# main_board_CHM.net
KiCad netlist of a schematic drawn in Altium Designer
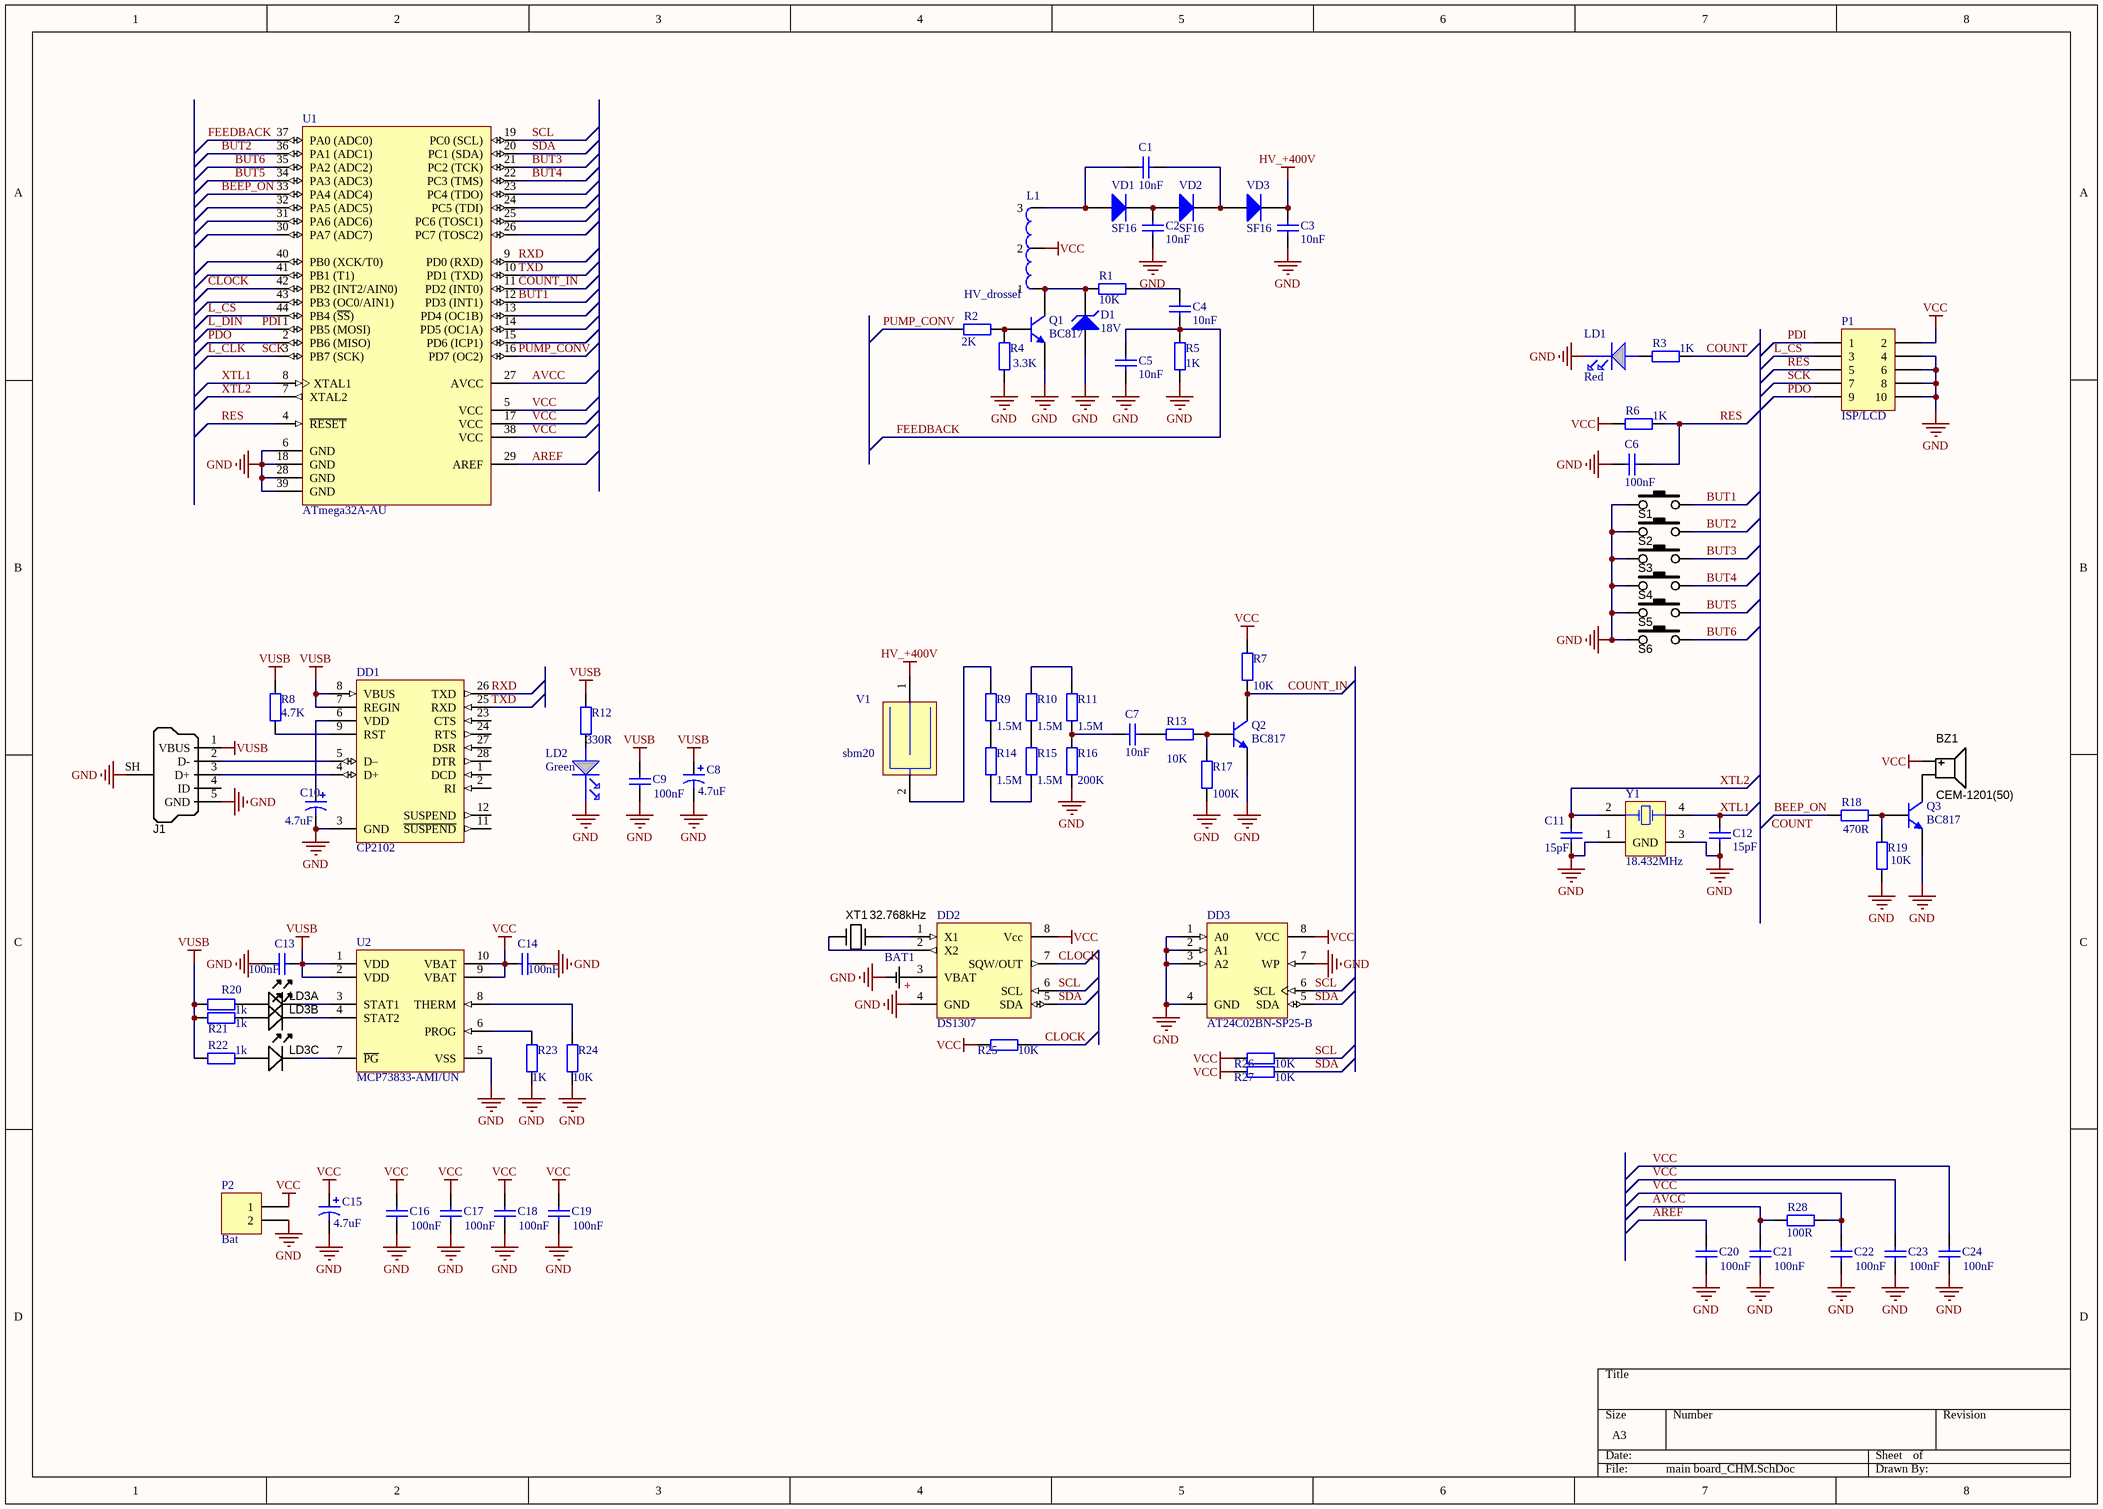
[diagram p0: main board_CHM.SchDoc]

(export (version "E")
  (design (tool "Eeschema 10.0.6"))
  (components
    (comp (ref "BAT1")
      (value "CH23-1220LF")
      (footprint "CH23-1220LF")
      (description "Battery holder")
      (libsource (lib "AX_Altium_v2.3") (part "CH23-1220LF"))
    )
    (comp (ref "BZ1")
      (value "Alternate part: 3100-932")
      (footprint "BUZZER_12.0X8.5MM")
      (description "Speaker, Magnetic Transducer")
      (fields (field (name "MANUFACTURER PART NUMBER 1") "CEM-1201(50)"))
      (libsource (lib "PBL - Electromechanical") (part "BZ_12x8.5x6.5_2kHz"))
    )
    (comp (ref "C1")
      (value "10nF")
      (footprint "CAPC3225X220N")
      (description "Ceramic Chip Capacitor - Standard")
      (fields (field (name "Comment") "C0805") (field (name "PUBLISHER") "Altium Limited"))
      (libsource (lib "KEMET Chip Capacitor") (part "C0805"))
    )
    (comp (ref "C2")
      (value "10nF")
      (footprint "CAPC3225X220N")
      (description "Ceramic Chip Capacitor - Standard")
      (fields (field (name "Comment") "C0805") (field (name "PUBLISHER") "Altium Limited"))
      (libsource (lib "KEMET Chip Capacitor") (part "C0805"))
    )
    (comp (ref "C3")
      (value "10nF")
      (footprint "CAPC3225X220N")
      (description "Ceramic Chip Capacitor - Standard")
      (fields (field (name "Comment") "C0805") (field (name "PUBLISHER") "Altium Limited"))
      (libsource (lib "KEMET Chip Capacitor") (part "C0805"))
    )
    (comp (ref "C4")
      (value "10nF")
      (footprint "CAPC2012X135N")
      (description "Ceramic Chip Capacitor - Standard")
      (fields (field (name "Comment") "C0805") (field (name "PUBLISHER") "Altium Limited"))
      (libsource (lib "KEMET Chip Capacitor") (part "C0805"))
    )
    (comp (ref "C5")
      (value "10nF")
      (footprint "CAPC2012X135N")
      (description "Ceramic Chip Capacitor - Standard")
      (fields (field (name "Comment") "C0805") (field (name "PUBLISHER") "Altium Limited"))
      (libsource (lib "KEMET Chip Capacitor") (part "C0805"))
    )
    (comp (ref "C6")
      (value "100nF")
      (footprint "CAPC2012X135N")
      (description "Ceramic Chip Capacitor - Standard")
      (fields (field (name "Comment") "C0805") (field (name "PUBLISHER") "Altium Limited"))
      (libsource (lib "KEMET Chip Capacitor") (part "C0805"))
    )
    (comp (ref "C7")
      (value "10nF")
      (footprint "CAPC2012X135N")
      (description "Ceramic Chip Capacitor - Standard")
      (fields (field (name "Comment") "C0805") (field (name "PUBLISHER") "Altium Limited"))
      (libsource (lib "KEMET Chip Capacitor") (part "C0805"))
    )
    (comp (ref "C8")
      (value "4.7uF")
      (footprint "CAPMP3216X180N")
      (description "Polarized Capacitor (Radial)")
      (fields (field (name "Comment") "Cap Pol1") (field (name "PUBLISHER") "Altium Limited"))
      (libsource (lib "Miscellaneous Devices") (part "Cap Pol1"))
    )
    (comp (ref "C9")
      (value "100nF")
      (footprint "CAPC2012X135N")
      (description "Ceramic Chip Capacitor - Standard")
      (fields (field (name "Comment") "C0805") (field (name "PUBLISHER") "Altium Limited"))
      (libsource (lib "KEMET Chip Capacitor") (part "C0805"))
    )
    (comp (ref "C10")
      (value "4.7uF")
      (footprint "CAPMP3216X180N")
      (description "Polarized Capacitor (Radial)")
      (fields (field (name "Comment") "Cap Pol1") (field (name "PUBLISHER") "Altium Limited"))
      (libsource (lib "Miscellaneous Devices") (part "Cap Pol1"))
    )
    (comp (ref "C11")
      (value "15pF")
      (footprint "CAPC2012X135N")
      (description "Ceramic Chip Capacitor - Standard")
      (fields (field (name "Comment") "C0805") (field (name "PUBLISHER") "Altium Limited"))
      (libsource (lib "KEMET Chip Capacitor") (part "C0805"))
    )
    (comp (ref "C12")
      (value "15pF")
      (footprint "CAPC2012X135N")
      (description "Ceramic Chip Capacitor - Standard")
      (fields (field (name "Comment") "C0805") (field (name "PUBLISHER") "Altium Limited"))
      (libsource (lib "KEMET Chip Capacitor") (part "C0805"))
    )
    (comp (ref "C13")
      (value "100nF")
      (footprint "CAPC2012X135N")
      (description "Ceramic Chip Capacitor - Standard")
      (fields (field (name "Comment") "C0805") (field (name "PUBLISHER") "Altium Limited"))
      (libsource (lib "KEMET Chip Capacitor") (part "C0805"))
    )
    (comp (ref "C14")
      (value "100nF")
      (footprint "CAPC2012X135N")
      (description "Ceramic Chip Capacitor - Standard")
      (fields (field (name "Comment") "C0805") (field (name "PUBLISHER") "Altium Limited"))
      (libsource (lib "KEMET Chip Capacitor") (part "C0805"))
    )
    (comp (ref "C15")
      (value "4.7uF")
      (footprint "CAPMP3216X180N")
      (description "Polarized Capacitor (Radial)")
      (fields (field (name "Comment") "Cap Pol1") (field (name "PUBLISHER") "Altium Limited"))
      (libsource (lib "Miscellaneous Devices") (part "Cap Pol1"))
    )
    (comp (ref "C16")
      (value "100nF")
      (footprint "CAPC2012X135N")
      (description "Ceramic Chip Capacitor - Standard")
      (fields (field (name "Comment") "C0805") (field (name "PUBLISHER") "Altium Limited"))
      (libsource (lib "KEMET Chip Capacitor") (part "C0805"))
    )
    (comp (ref "C17")
      (value "100nF")
      (footprint "CAPC2012X135N")
      (description "Ceramic Chip Capacitor - Standard")
      (fields (field (name "Comment") "C0805") (field (name "PUBLISHER") "Altium Limited"))
      (libsource (lib "KEMET Chip Capacitor") (part "C0805"))
    )
    (comp (ref "C18")
      (value "100nF")
      (footprint "CAPC2012X135N")
      (description "Ceramic Chip Capacitor - Standard")
      (fields (field (name "Comment") "C0805") (field (name "PUBLISHER") "Altium Limited"))
      (libsource (lib "KEMET Chip Capacitor") (part "C0805"))
    )
    (comp (ref "C19")
      (value "100nF")
      (footprint "CAPC2012X135N")
      (description "Ceramic Chip Capacitor - Standard")
      (fields (field (name "Comment") "C0805") (field (name "PUBLISHER") "Altium Limited"))
      (libsource (lib "KEMET Chip Capacitor") (part "C0805"))
    )
    (comp (ref "C20")
      (value "100nF")
      (footprint "CAPC2012X135N")
      (description "Ceramic Chip Capacitor - Standard")
      (fields (field (name "Comment") "C0805") (field (name "PUBLISHER") "Altium Limited"))
      (libsource (lib "KEMET Chip Capacitor") (part "C0805"))
    )
    (comp (ref "C21")
      (value "100nF")
      (footprint "CAPC2012X135N")
      (description "Ceramic Chip Capacitor - Standard")
      (fields (field (name "Comment") "C0805") (field (name "PUBLISHER") "Altium Limited"))
      (libsource (lib "KEMET Chip Capacitor") (part "C0805"))
    )
    (comp (ref "C22")
      (value "100nF")
      (footprint "CAPC2012X135N")
      (description "Ceramic Chip Capacitor - Standard")
      (fields (field (name "Comment") "C0805") (field (name "PUBLISHER") "Altium Limited"))
      (libsource (lib "KEMET Chip Capacitor") (part "C0805"))
    )
    (comp (ref "C23")
      (value "100nF")
      (footprint "CAPC2012X135N")
      (description "Ceramic Chip Capacitor - Standard")
      (fields (field (name "Comment") "C0805") (field (name "PUBLISHER") "Altium Limited"))
      (libsource (lib "KEMET Chip Capacitor") (part "C0805"))
    )
    (comp (ref "C24")
      (value "100nF")
      (footprint "CAPC2012X135N")
      (description "Ceramic Chip Capacitor - Standard")
      (fields (field (name "Comment") "C0805") (field (name "PUBLISHER") "Altium Limited"))
      (libsource (lib "KEMET Chip Capacitor") (part "C0805"))
    )
    (comp (ref "D1")
      (value "18V")
      (footprint "DO-214AC")
      (description "Zener Diode")
      (fields (field (name "PUBLISHER") "Altium Limited"))
      (libsource (lib "Miscellaneous Devices") (part "D Zener"))
    )
    (comp (ref "DD1") (value "CP2102") (footprint "32-QFN_M") (libsource (lib "CP2102") (part "CP2102")))
    (comp (ref "DD2")
      (value "DS1307")
      (footprint "SOIC127P600X175-8AN")
      (libsource (lib "DS1307") (part "DS1307"))
    )
    (comp (ref "DD3")
      (value "AT24C02BN-SP25-B")
      (footprint "SOIC127P600X175-8AN")
      (fields (field (name "PUBLISHER") "Altium Limited"))
      (libsource (lib "Atmel Memory Serial EEPROM") (part "AT24C02BN-SP25-B"))
    )
    (comp (ref "J1")
      (value "USB Micro Type B (recommended if hand soldering)")
      (footprint "USB_micro_VTN")
      (description "Connector SMD-THD USB Micro Type B middle mount")
      (libsource (lib "PBL - Connectors") (part "USB_Micro_TypeB_FCI"))
    )
    (comp (ref "L1")
      (value "HV_drossel")
      (footprint "HV_drossel")
      (libsource (lib "HV_drossel") (part "HV_drossel"))
    )
    (comp (ref "LD1")
      (value "Red")
      (footprint "LED-0603-RED")
      (description "APT1608QBC/D")
      (fields (field (name "Comment") "PWR_H"))
      (libsource (lib "discret") (part "LED"))
    )
    (comp (ref "LD2")
      (value "Green")
      (footprint "LED-0603-GREEN")
      (description "APT1608QBC/D")
      (fields (field (name "Comment") "PWR_H"))
      (libsource (lib "discret") (part "LED"))
    )
    (comp (ref "LD3")
      (value "Power status")
      (footprint "LED_3-HIGH_3MM")
      (description "LED array PCB mount 3-high 3mm green")
      (libsource (lib "PBL - Light Sources") (part "LEDPACK_GREEN_3HIGH_3MM"))
    )
    (comp (ref "P1")
      (value "ISP/LCD")
      (footprint "10P_PCB_HEADER_BRD_MNT")
      (description "Header, 5-Pin, Dual row")
      (fields (field (name "PUBLISHER") "Altium Limited"))
      (libsource (lib "Miscellaneous Connectors") (part "Header 5X2"))
    )
    (comp (ref "P2")
      (value "Bat")
      (footprint "HDR1X2")
      (description "Header, 2-Pin")
      (fields (field (name "PUBLISHER") "Altium Limited"))
      (libsource (lib "Miscellaneous Connectors") (part "Header 2"))
    )
    (comp (ref "Q1")
      (value "BC817")
      (footprint "SOT23-3")
      (description "NPN Bipolar Transistor")
      (fields (field (name "PUBLISHER") "Altium Limited"))
      (libsource (lib "Miscellaneous Devices") (part "QNPN"))
    )
    (comp (ref "Q2")
      (value "BC817")
      (footprint "SOT23-3")
      (description "NPN Bipolar Transistor")
      (fields (field (name "PUBLISHER") "Altium Limited"))
      (libsource (lib "Miscellaneous Devices") (part "QNPN"))
    )
    (comp (ref "Q3")
      (value "BC817")
      (footprint "SOT23-3")
      (description "NPN Bipolar Transistor")
      (fields (field (name "PUBLISHER") "Altium Limited"))
      (libsource (lib "Miscellaneous Devices") (part "QNPN"))
    )
    (comp (ref "R1")
      (value "10K")
      (footprint "RESC2012X70N")
      (description "Resistor")
      (fields (field (name "Comment") "Res2") (field (name "PUBLISHER") "Altium Limited"))
      (libsource (lib "") (part "Res2_2"))
    )
    (comp (ref "R2")
      (value "2K")
      (footprint "RESC2012X70N")
      (description "Resistor")
      (fields (field (name "Comment") "Res2") (field (name "PUBLISHER") "Altium Limited"))
      (libsource (lib "Miscellaneous Devices") (part "Res2"))
    )
    (comp (ref "R3")
      (value "1K")
      (footprint "RESC2012X70N")
      (description "Resistor")
      (fields (field (name "Comment") "Res2") (field (name "PUBLISHER") "Altium Limited"))
      (libsource (lib "Miscellaneous Devices") (part "Res2"))
    )
    (comp (ref "R4")
      (value "3.3K")
      (footprint "RESC2012X70N")
      (description "Resistor")
      (fields (field (name "Comment") "Res2") (field (name "PUBLISHER") "Altium Limited"))
      (libsource (lib "") (part "Res2_1"))
    )
    (comp (ref "R5")
      (value "1K")
      (footprint "RESC2012X70N")
      (description "Resistor")
      (fields (field (name "Comment") "Res2") (field (name "PUBLISHER") "Altium Limited"))
      (libsource (lib "") (part "Res2_1"))
    )
    (comp (ref "R6")
      (value "1K")
      (footprint "RESC2012X70N")
      (description "Resistor")
      (fields (field (name "Comment") "Res2") (field (name "PUBLISHER") "Altium Limited"))
      (libsource (lib "Miscellaneous Devices") (part "Res2"))
    )
    (comp (ref "R7")
      (value "10K")
      (footprint "RESC2012X70N")
      (description "Resistor")
      (fields (field (name "Comment") "Res2") (field (name "PUBLISHER") "Altium Limited"))
      (libsource (lib "") (part "Res2_1"))
    )
    (comp (ref "R8")
      (value "4.7K")
      (footprint "RESC2012X70N")
      (description "Resistor")
      (fields (field (name "Comment") "Res2") (field (name "PUBLISHER") "Altium Limited"))
      (libsource (lib "") (part "Res2_1"))
    )
    (comp (ref "R9")
      (value "1.5M")
      (footprint "RESC3216X70N")
      (description "Resistor")
      (fields (field (name "Comment") "Res2") (field (name "PUBLISHER") "Altium Limited"))
      (libsource (lib "") (part "Res2_1"))
    )
    (comp (ref "R10")
      (value "1.5M")
      (footprint "RESC3216X70N")
      (description "Resistor")
      (fields (field (name "Comment") "Res2") (field (name "PUBLISHER") "Altium Limited"))
      (libsource (lib "") (part "Res2_1"))
    )
    (comp (ref "R11")
      (value "1.5M")
      (footprint "RESC3216X70N")
      (description "Resistor")
      (fields (field (name "Comment") "Res2") (field (name "PUBLISHER") "Altium Limited"))
      (libsource (lib "") (part "Res2_1"))
    )
    (comp (ref "R12")
      (value "330R")
      (footprint "RESC2012X70N")
      (description "Resistor")
      (fields (field (name "Comment") "Res2") (field (name "PUBLISHER") "Altium Limited"))
      (libsource (lib "") (part "Res2_1"))
    )
    (comp (ref "R13")
      (value "10K")
      (footprint "RESC2012X70N")
      (description "Resistor")
      (fields (field (name "Comment") "Res2") (field (name "PUBLISHER") "Altium Limited"))
      (libsource (lib "Miscellaneous Devices") (part "Res2"))
    )
    (comp (ref "R14")
      (value "1.5M")
      (footprint "RESC3216X70N")
      (description "Resistor")
      (fields (field (name "Comment") "Res2") (field (name "PUBLISHER") "Altium Limited"))
      (libsource (lib "") (part "Res2_1"))
    )
    (comp (ref "R15")
      (value "1.5M")
      (footprint "RESC3216X70N")
      (description "Resistor")
      (fields (field (name "Comment") "Res2") (field (name "PUBLISHER") "Altium Limited"))
      (libsource (lib "") (part "Res2_1"))
    )
    (comp (ref "R16")
      (value "200K")
      (footprint "RESC3216X70N")
      (description "Resistor")
      (fields (field (name "Comment") "Res2") (field (name "PUBLISHER") "Altium Limited"))
      (libsource (lib "") (part "Res2_1"))
    )
    (comp (ref "R17")
      (value "100K")
      (footprint "RESC2012X70N")
      (description "Resistor")
      (fields (field (name "Comment") "Res2") (field (name "PUBLISHER") "Altium Limited"))
      (libsource (lib "") (part "Res2_1"))
    )
    (comp (ref "R18")
      (value "470R")
      (footprint "RESC2012X70N")
      (description "Resistor")
      (fields (field (name "Comment") "Res2") (field (name "PUBLISHER") "Altium Limited"))
      (libsource (lib "Miscellaneous Devices") (part "Res2"))
    )
    (comp (ref "R19")
      (value "10K")
      (footprint "RESC2012X70N")
      (description "Resistor")
      (fields (field (name "Comment") "Res2") (field (name "PUBLISHER") "Altium Limited"))
      (libsource (lib "") (part "Res2_1"))
    )
    (comp (ref "R20")
      (value "1k")
      (footprint "RESC2012X70N")
      (description "Resistor")
      (fields (field (name "Comment") "Res2") (field (name "PUBLISHER") "Altium Limited"))
      (libsource (lib "Miscellaneous Devices") (part "Res2"))
    )
    (comp (ref "R21")
      (value "1k")
      (footprint "RESC2012X70N")
      (description "Resistor")
      (fields (field (name "Comment") "Res2") (field (name "PUBLISHER") "Altium Limited"))
      (libsource (lib "Miscellaneous Devices") (part "Res2"))
    )
    (comp (ref "R22")
      (value "1k")
      (footprint "RESC2012X70N")
      (description "Resistor")
      (fields (field (name "Comment") "Res2") (field (name "PUBLISHER") "Altium Limited"))
      (libsource (lib "Miscellaneous Devices") (part "Res2"))
    )
    (comp (ref "R23")
      (value "1K")
      (footprint "RESC2012X70N")
      (description "Resistor")
      (fields (field (name "Comment") "Res2") (field (name "PUBLISHER") "Altium Limited"))
      (libsource (lib "") (part "Res2_1"))
    )
    (comp (ref "R24")
      (value "10K")
      (footprint "HDR1X2")
      (description "Resistor")
      (fields (field (name "Comment") "Res2") (field (name "PUBLISHER") "Altium Limited"))
      (libsource (lib "") (part "Res2_1"))
    )
    (comp (ref "R25")
      (value "10K")
      (footprint "6-0805_N")
      (description "Resistor")
      (fields (field (name "Comment") "Res2") (field (name "PUBLISHER") "Altium Limited"))
      (libsource (lib "") (part "Res2_2"))
    )
    (comp (ref "R26")
      (value "10K")
      (footprint "6-0805_N")
      (description "Resistor")
      (fields (field (name "Comment") "Res2") (field (name "PUBLISHER") "Altium Limited"))
      (libsource (lib "") (part "Res2_2"))
    )
    (comp (ref "R27")
      (value "10K")
      (footprint "6-0805_N")
      (description "Resistor")
      (fields (field (name "Comment") "Res2") (field (name "PUBLISHER") "Altium Limited"))
      (libsource (lib "") (part "Res2_2"))
    )
    (comp (ref "R28")
      (value "100R")
      (footprint "RESC2012X70N")
      (description "Resistor")
      (fields (field (name "Comment") "Res2") (field (name "PUBLISHER") "Altium Limited"))
      (libsource (lib "Miscellaneous Devices") (part "Res2"))
    )
    (comp (ref "S1")
      (value "SW_THT_PB_7.0mm")
      (footprint "KEY_L_F")
      (description "Switch, tact, 7.0mm stem")
      (libsource (lib "PBL - Switches") (part "SW_THT_PB_7.0mm"))
    )
    (comp (ref "S2")
      (value "SW_THT_PB_7.0mm")
      (footprint "KEY_L_F")
      (description "Switch, tact, 7.0mm stem")
      (libsource (lib "PBL - Switches") (part "SW_THT_PB_7.0mm"))
    )
    (comp (ref "S3")
      (value "SW_THT_PB_7.0mm")
      (footprint "KEY_L_F")
      (description "Switch, tact, 7.0mm stem")
      (libsource (lib "PBL - Switches") (part "SW_THT_PB_7.0mm"))
    )
    (comp (ref "S4")
      (value "SW_THT_PB_7.0mm")
      (footprint "KEY_L_F")
      (description "Switch, tact, 7.0mm stem")
      (libsource (lib "PBL - Switches") (part "SW_THT_PB_7.0mm"))
    )
    (comp (ref "S5")
      (value "SW_THT_PB_7.0mm")
      (footprint "KEY_L_F")
      (description "Switch, tact, 7.0mm stem")
      (libsource (lib "PBL - Switches") (part "SW_THT_PB_7.0mm"))
    )
    (comp (ref "S6")
      (value "SW_THT_PB_7.0mm")
      (footprint "KEY_L_F")
      (description "Switch, tact, 7.0mm stem")
      (libsource (lib "PBL - Switches") (part "SW_THT_PB_7.0mm"))
    )
    (comp (ref "U1")
      (value "ATmega32A-AU")
      (footprint "44A_N")
      (fields (field (name "PUBLISHER") "Altium Limited"))
      (libsource (lib "Atmel Microcontroller 8-Bit megaAVR") (part "ATmega32A-AU"))
    )
    (comp (ref "U2")
      (value "MCP73833-AMI/UN")
      (footprint "MSOP-UN10_L")
      (fields (field (name "PUBLISHER") "Altium Limited"))
      (libsource (lib "Microchip Power Mgt Battery Management") (part "MCP73833-AMI/UN"))
    )
    (comp (ref "V1") (value "sbm20") (footprint "sbm20") (libsource (lib "sbm20") (part "K1.1")))
    (comp (ref "VD1")
      (value "SF16")
      (footprint "DO-214AC")
      (description "1 Amp General Purpose Rectifier")
      (fields (field (name "PUBLISHER") "Altium Limited"))
      (libsource (lib "Miscellaneous Devices") (part "Diode 1N4001"))
    )
    (comp (ref "VD2")
      (value "SF16")
      (footprint "DO-214AC")
      (description "1 Amp General Purpose Rectifier")
      (fields (field (name "PUBLISHER") "Altium Limited"))
      (libsource (lib "Miscellaneous Devices") (part "Diode 1N4001"))
    )
    (comp (ref "VD3")
      (value "SF16")
      (footprint "DO-214AC")
      (description "1 Amp General Purpose Rectifier")
      (fields (field (name "PUBLISHER") "Altium Limited"))
      (libsource (lib "Miscellaneous Devices") (part "Diode 1N4001"))
    )
    (comp (ref "XT1")
      (value "32.768kHz")
      (footprint "CRYSTAL_CMR309T")
      (description "Resonator Ceramic 6.00 MHz 30ppm")
      (fields (field (name "TOLERANCE") "±50ppm"))
      (libsource (lib "PBL - Resonators") (part "Crystal_6MHz_CMR309T"))
    )
    (comp (ref "Y1")
      (value "18.432MHz")
      (footprint "0532(MJ)")
      (description "Crystal Oscillator")
      (libsource (lib "AX_Altium_v2.3") (part "Y_0532(MJ)"))
    )
  )
  (nets
    (net (code "1") (name "/AREF") (class "Default")
      (node (ref "C20") (pin "2") (pinfunction "2_2") (pintype "passive"))
      (node (ref "U1") (pin "29") (pinfunction "AREF_29") (pintype "power_in"))
    )
    (net (code "2") (name "/AVCC") (class "Default")
      (node (ref "C21") (pin "2") (pinfunction "2_2") (pintype "passive"))
      (node (ref "R28") (pin "1") (pinfunction "1_1") (pintype "passive"))
      (node (ref "U1") (pin "27") (pinfunction "AVCC_27") (pintype "power_in"))
    )
    (net (code "3") (name "/BEEP_ON") (class "Default")
      (node (ref "R18") (pin "1") (pinfunction "1_1") (pintype "passive"))
      (node (ref "R3") (pin "2") (pinfunction "2_2") (pintype "passive"))
      (node (ref "U1") (pin "33") (pinfunction "PA4_(ADC4)_33") (pintype "bidirectional"))
    )
    (net (code "4") (name "/BUT1") (class "Default")
      (node (ref "S1") (pin "1") (pintype "passive"))
      (node (ref "U1") (pin "12") (pinfunction "PD3_(INT1)_12") (pintype "bidirectional"))
    )
    (net (code "5") (name "/BUT2") (class "Default")
      (node (ref "S2") (pin "1") (pintype "passive"))
      (node (ref "U1") (pin "36") (pinfunction "PA1_(ADC1)_36") (pintype "bidirectional"))
    )
    (net (code "6") (name "/BUT3") (class "Default")
      (node (ref "S3") (pin "1") (pintype "passive"))
      (node (ref "U1") (pin "21") (pinfunction "PC2_(TCK)_21") (pintype "bidirectional"))
    )
    (net (code "7") (name "/BUT4") (class "Default")
      (node (ref "S4") (pin "1") (pintype "passive"))
      (node (ref "U1") (pin "22") (pinfunction "PC3_(TMS)_22") (pintype "bidirectional"))
    )
    (net (code "8") (name "/BUT5") (class "Default")
      (node (ref "S5") (pin "1") (pintype "passive"))
      (node (ref "U1") (pin "34") (pinfunction "PA3_(ADC3)_34") (pintype "bidirectional"))
    )
    (net (code "9") (name "/BUT6") (class "Default")
      (node (ref "S6") (pin "1") (pintype "passive"))
      (node (ref "U1") (pin "35") (pinfunction "PA2_(ADC2)_35") (pintype "bidirectional"))
    )
    (net (code "10") (name "/CLOCK") (class "Default")
      (node (ref "DD2") (pin "7") (pinfunction "SQW/OUT_7") (pintype "output"))
      (node (ref "R25") (pin "1") (pinfunction "1_1") (pintype "passive"))
      (node (ref "U1") (pin "42") (pinfunction "PB2_(INT2/AIN0)_42") (pintype "bidirectional"))
    )
    (net (code "11") (name "/COUNT_IN") (class "Default")
      (node (ref "Q2") (pin "1") (pinfunction "C_1") (pintype "passive"))
      (node (ref "R7") (pin "1") (pinfunction "1_1") (pintype "passive"))
      (node (ref "U1") (pin "11") (pinfunction "PD2_(INT0)_11") (pintype "bidirectional"))
    )
    (net (code "12") (name "/FEEDBACK") (class "Default")
      (node (ref "C4") (pin "1") (pinfunction "1_1") (pintype "passive"))
      (node (ref "C5") (pin "1") (pinfunction "1_1") (pintype "passive"))
      (node (ref "R5") (pin "2") (pinfunction "2_2") (pintype "passive"))
      (node (ref "U1") (pin "37") (pinfunction "PA0_(ADC0)_37") (pintype "bidirectional"))
    )
    (net (code "13") (name "/L_CLK") (class "Default")
      (node (ref "P1") (pin "7") (pinfunction "7_7") (pintype "passive"))
      (node (ref "U1") (pin "3") (pinfunction "PB7_(SCK)_3") (pintype "bidirectional"))
    )
    (net (code "14") (name "/L_CS") (class "Default")
      (node (ref "P1") (pin "3") (pinfunction "3_3") (pintype "passive"))
      (node (ref "U1") (pin "44") (pinfunction "PB4_(~{SS})_44") (pintype "bidirectional"))
    )
    (net (code "15") (name "/L_DIN") (class "Default")
      (node (ref "P1") (pin "1") (pinfunction "1_1") (pintype "passive"))
      (node (ref "U1") (pin "1") (pinfunction "PB5_(MOSI)_1") (pintype "bidirectional"))
    )
    (net (code "16") (name "/PDO") (class "Default")
      (node (ref "P1") (pin "9") (pinfunction "9_9") (pintype "passive"))
      (node (ref "U1") (pin "2") (pinfunction "PB6_(MISO)_2") (pintype "bidirectional"))
    )
    (net (code "17") (name "/PUMP_CONV") (class "Default")
      (node (ref "R2") (pin "1") (pinfunction "1_1") (pintype "passive"))
      (node (ref "U1") (pin "16") (pinfunction "PD7_(OC2)_16") (pintype "bidirectional"))
    )
    (net (code "18") (name "/RES") (class "Default")
      (node (ref "C6") (pin "1") (pinfunction "1_1") (pintype "passive"))
      (node (ref "P1") (pin "5") (pinfunction "5_5") (pintype "passive"))
      (node (ref "R6") (pin "2") (pinfunction "2_2") (pintype "passive"))
      (node (ref "U1") (pin "4") (pinfunction "~{RESET}_4") (pintype "input"))
    )
    (net (code "19") (name "/RXD") (class "Default")
      (node (ref "DD1") (pin "26") (pinfunction "TXD_26") (pintype "output"))
      (node (ref "U1") (pin "9") (pinfunction "PD0_(RXD)_9") (pintype "bidirectional"))
    )
    (net (code "20") (name "/SCL") (class "Default")
      (node (ref "DD2") (pin "6") (pinfunction "SCL_6") (pintype "input"))
      (node (ref "DD3") (pin "6") (pinfunction "SCL_6") (pintype "input"))
      (node (ref "R26") (pin "1") (pinfunction "1_1") (pintype "passive"))
      (node (ref "U1") (pin "19") (pinfunction "PC0_(SCL)_19") (pintype "bidirectional"))
    )
    (net (code "21") (name "/SDA") (class "Default")
      (node (ref "DD2") (pin "5") (pinfunction "SDA_5") (pintype "bidirectional"))
      (node (ref "DD3") (pin "5") (pinfunction "SDA_5") (pintype "bidirectional"))
      (node (ref "R27") (pin "1") (pinfunction "1_1") (pintype "passive"))
      (node (ref "U1") (pin "20") (pinfunction "PC1_(SDA)_20") (pintype "bidirectional"))
    )
    (net (code "22") (name "/TXD") (class "Default")
      (node (ref "DD1") (pin "25") (pinfunction "RXD_25") (pintype "input"))
      (node (ref "U1") (pin "10") (pinfunction "PD1_(TXD)_10") (pintype "bidirectional"))
    )
    (net (code "23") (name "/XTL1") (class "Default")
      (node (ref "C12") (pin "2") (pinfunction "2_2") (pintype "passive"))
      (node (ref "U1") (pin "8") (pinfunction "XTAL1_8") (pintype "input"))
      (node (ref "Y1") (pin "4") (pinfunction "OSC2_4") (pintype "passive"))
    )
    (net (code "24") (name "/XTL2") (class "Default")
      (node (ref "C11") (pin "2") (pinfunction "2_2") (pintype "passive"))
      (node (ref "U1") (pin "7") (pinfunction "XTAL2_7") (pintype "output"))
      (node (ref "Y1") (pin "2") (pinfunction "OSC1_2") (pintype "passive"))
    )
    (net (code "25") (name "GND") (class "Default")
      (node (ref "BAT1") (pin "0") (pinfunction "0_0") (pintype "passive"))
      (node (ref "C10") (pin "2") (pinfunction "2_2") (pintype "passive"))
      (node (ref "C11") (pin "1") (pinfunction "1_1") (pintype "passive"))
      (node (ref "C12") (pin "1") (pinfunction "1_1") (pintype "passive"))
      (node (ref "C13") (pin "2") (pinfunction "2_2") (pintype "passive"))
      (node (ref "C14") (pin "1") (pinfunction "1_1") (pintype "passive"))
      (node (ref "C15") (pin "2") (pinfunction "2_2") (pintype "passive"))
      (node (ref "C16") (pin "1") (pinfunction "1_1") (pintype "passive"))
      (node (ref "C17") (pin "1") (pinfunction "1_1") (pintype "passive"))
      (node (ref "C18") (pin "1") (pinfunction "1_1") (pintype "passive"))
      (node (ref "C19") (pin "1") (pinfunction "1_1") (pintype "passive"))
      (node (ref "C2") (pin "2") (pinfunction "2_2") (pintype "passive"))
      (node (ref "C20") (pin "1") (pinfunction "1_1") (pintype "passive"))
      (node (ref "C21") (pin "1") (pinfunction "1_1") (pintype "passive"))
      (node (ref "C22") (pin "1") (pinfunction "1_1") (pintype "passive"))
      (node (ref "C23") (pin "1") (pinfunction "1_1") (pintype "passive"))
      (node (ref "C24") (pin "1") (pinfunction "1_1") (pintype "passive"))
      (node (ref "C3") (pin "2") (pinfunction "2_2") (pintype "passive"))
      (node (ref "C5") (pin "2") (pinfunction "2_2") (pintype "passive"))
      (node (ref "C6") (pin "2") (pinfunction "2_2") (pintype "passive"))
      (node (ref "C8") (pin "2") (pinfunction "2_2") (pintype "passive"))
      (node (ref "C9") (pin "1") (pinfunction "1_1") (pintype "passive"))
      (node (ref "D1") (pin "1") (pinfunction "A_1") (pintype "passive"))
      (node (ref "DD1") (pin "3") (pinfunction "GND_3") (pintype "power_in"))
      (node (ref "DD2") (pin "4") (pinfunction "GND_4") (pintype "power_in"))
      (node (ref "DD3") (pin "1") (pinfunction "A0_1") (pintype "input"))
      (node (ref "DD3") (pin "2") (pinfunction "A1_2") (pintype "input"))
      (node (ref "DD3") (pin "3") (pinfunction "A2_3") (pintype "input"))
      (node (ref "DD3") (pin "4") (pinfunction "GND_4") (pintype "power_in"))
      (node (ref "DD3") (pin "7") (pinfunction "WP_7") (pintype "input"))
      (node (ref "J1") (pin "5") (pinfunction "GND_5") (pintype "passive"))
      (node (ref "J1") (pin "SH") (pinfunction "Shell_SH") (pintype "passive"))
      (node (ref "LD1") (pin "K") (pinfunction "CATODE_K") (pintype "passive"))
      (node (ref "LD2") (pin "K") (pinfunction "CATODE_K") (pintype "passive"))
      (node (ref "P1") (pin "10") (pinfunction "10_10") (pintype "passive"))
      (node (ref "P1") (pin "4") (pinfunction "4_4") (pintype "passive"))
      (node (ref "P1") (pin "6") (pinfunction "6_6") (pintype "passive"))
      (node (ref "P1") (pin "8") (pinfunction "8_8") (pintype "passive"))
      (node (ref "P2") (pin "2") (pinfunction "2_2") (pintype "passive"))
      (node (ref "Q1") (pin "3") (pinfunction "E_3") (pintype "passive"))
      (node (ref "Q2") (pin "3") (pinfunction "E_3") (pintype "passive"))
      (node (ref "Q3") (pin "3") (pinfunction "E_3") (pintype "passive"))
      (node (ref "R16") (pin "1") (pinfunction "1_1") (pintype "passive"))
      (node (ref "R17") (pin "1") (pinfunction "1_1") (pintype "passive"))
      (node (ref "R19") (pin "1") (pinfunction "1_1") (pintype "passive"))
      (node (ref "R23") (pin "1") (pinfunction "1_1") (pintype "passive"))
      (node (ref "R24") (pin "1") (pinfunction "1_1") (pintype "passive"))
      (node (ref "R4") (pin "1") (pinfunction "1_1") (pintype "passive"))
      (node (ref "R5") (pin "1") (pinfunction "1_1") (pintype "passive"))
      (node (ref "S1") (pin "2") (pintype "passive"))
      (node (ref "S2") (pin "2") (pintype "passive"))
      (node (ref "S3") (pin "2") (pintype "passive"))
      (node (ref "S4") (pin "2") (pintype "passive"))
      (node (ref "S5") (pin "2") (pintype "passive"))
      (node (ref "S6") (pin "2") (pintype "passive"))
      (node (ref "U1") (pin "18") (pinfunction "GND_18") (pintype "power_in"))
      (node (ref "U1") (pin "28") (pinfunction "GND_28") (pintype "power_in"))
      (node (ref "U1") (pin "39") (pinfunction "GND_39") (pintype "power_in"))
      (node (ref "U1") (pin "6") (pinfunction "GND_6") (pintype "power_in"))
      (node (ref "U2") (pin "5") (pinfunction "VSS_5") (pintype "power_in"))
      (node (ref "Y1") (pin "1") (pinfunction "GND_1") (pintype "passive"))
      (node (ref "Y1") (pin "3") (pinfunction "GND_3") (pintype "passive"))
    )
    (net (code "26") (name "HV_+400V") (class "Default")
      (node (ref "C3") (pin "1") (pinfunction "1_1") (pintype "passive"))
      (node (ref "V1") (pin "1") (pintype "power_in"))
      (node (ref "VD3") (pin "2") (pinfunction "K_2") (pintype "passive"))
    )
    (net (code "27") (name "Net-(BZ1-Negative)") (class "Default")
      (node (ref "BZ1") (pin "2") (pinfunction "Negative_2") (pintype "passive"))
      (node (ref "Q3") (pin "1") (pinfunction "C_1") (pintype "passive"))
    )
    (net (code "28") (name "Net-(C4-Pad2)") (class "Default")
      (node (ref "C4") (pin "2") (pinfunction "2_2") (pintype "passive"))
      (node (ref "R1") (pin "1") (pinfunction "1_1") (pintype "passive"))
    )
    (net (code "29") (name "Net-(C7-Pad1)") (class "Default")
      (node (ref "C7") (pin "1") (pinfunction "1_1") (pintype "passive"))
      (node (ref "R13") (pin "1") (pinfunction "1_1") (pintype "passive"))
    )
    (net (code "30") (name "Net-(C7-Pad2)") (class "Default")
      (node (ref "C7") (pin "2") (pinfunction "2_2") (pintype "passive"))
      (node (ref "R11") (pin "1") (pinfunction "1_1") (pintype "passive"))
      (node (ref "R16") (pin "2") (pinfunction "2_2") (pintype "passive"))
    )
    (net (code "31") (name "Net-(D1-K)") (class "Default")
      (node (ref "D1") (pin "2") (pinfunction "K_2") (pintype "passive"))
      (node (ref "L1") (pin "1") (pinfunction "1_1") (pintype "passive"))
      (node (ref "Q1") (pin "1") (pinfunction "C_1") (pintype "passive"))
      (node (ref "R1") (pin "2") (pinfunction "2_2") (pintype "passive"))
    )
    (net (code "32") (name "Net-(DD1-D+)") (class "Default")
      (node (ref "DD1") (pin "4") (pinfunction "D+_4") (pintype "bidirectional"))
      (node (ref "J1") (pin "3") (pinfunction "D+_3") (pintype "passive"))
    )
    (net (code "33") (name "Net-(DD1-D–)") (class "Default")
      (node (ref "DD1") (pin "5") (pinfunction "D–_5") (pintype "bidirectional"))
      (node (ref "J1") (pin "2") (pinfunction "D-_2") (pintype "passive"))
    )
    (net (code "34") (name "Net-(DD1-RST)") (class "Default")
      (node (ref "DD1") (pin "9") (pinfunction "RST_9") (pintype "power_in"))
      (node (ref "R8") (pin "1") (pinfunction "1_1") (pintype "passive"))
    )
    (net (code "35") (name "Net-(DD1-VDD)") (class "Default")
      (node (ref "C10") (pin "1") (pinfunction "1_1") (pintype "passive"))
      (node (ref "DD1") (pin "6") (pinfunction "VDD_6") (pintype "power_in"))
    )
    (net (code "36") (name "Net-(DD2-VBAT)") (class "Default")
      (node (ref "BAT1") (pin "1") (pinfunction "1_1") (pintype "passive"))
      (node (ref "DD2") (pin "3") (pinfunction "VBAT_3") (pintype "power_in"))
    )
    (net (code "37") (name "Net-(DD2-X1)") (class "Default")
      (node (ref "DD2") (pin "1") (pinfunction "X1_1") (pintype "input"))
      (node (ref "XT1") (pin "2") (pinfunction "OUT_2") (pintype "passive"))
    )
    (net (code "38") (name "Net-(DD2-X2)") (class "Default")
      (node (ref "DD2") (pin "2") (pinfunction "X2_2") (pintype "output"))
      (node (ref "XT1") (pin "1") (pinfunction "IN_1") (pintype "passive"))
    )
    (net (code "39") (name "Net-(LD1-ANODE)") (class "Default")
      (node (ref "LD1") (pin "A") (pinfunction "ANODE_A") (pintype "passive"))
      (node (ref "R3") (pin "1") (pinfunction "1_1") (pintype "passive"))
    )
    (net (code "40") (name "Net-(LD2-ANODE)") (class "Default")
      (node (ref "LD2") (pin "A") (pinfunction "ANODE_A") (pintype "passive"))
      (node (ref "R12") (pin "1") (pinfunction "1_1") (pintype "passive"))
    )
    (net (code "41") (name "Net-(LD3-PadA1)") (class "Default")
      (node (ref "LD3") (pin "A1") (pinfunction "A1_A1") (pintype "passive"))
      (node (ref "R20") (pin "2") (pinfunction "2_2") (pintype "passive"))
    )
    (net (code "42") (name "Net-(LD3-PadA2)") (class "Default")
      (node (ref "LD3") (pin "A2") (pinfunction "A2_A2") (pintype "passive"))
      (node (ref "R21") (pin "2") (pinfunction "2_2") (pintype "passive"))
    )
    (net (code "43") (name "Net-(LD3-PadA3)") (class "Default")
      (node (ref "LD3") (pin "A3") (pinfunction "A3_A3") (pintype "passive"))
      (node (ref "R22") (pin "2") (pinfunction "2_2") (pintype "passive"))
    )
    (net (code "44") (name "Net-(Q1-B)") (class "Default")
      (node (ref "Q1") (pin "2") (pinfunction "B_2") (pintype "passive"))
      (node (ref "R2") (pin "2") (pinfunction "2_2") (pintype "passive"))
      (node (ref "R4") (pin "2") (pinfunction "2_2") (pintype "passive"))
    )
    (net (code "45") (name "Net-(Q2-B)") (class "Default")
      (node (ref "Q2") (pin "2") (pinfunction "B_2") (pintype "passive"))
      (node (ref "R13") (pin "2") (pinfunction "2_2") (pintype "passive"))
      (node (ref "R17") (pin "2") (pinfunction "2_2") (pintype "passive"))
    )
    (net (code "46") (name "Net-(Q3-B)") (class "Default")
      (node (ref "Q3") (pin "2") (pinfunction "B_2") (pintype "passive"))
      (node (ref "R18") (pin "2") (pinfunction "2_2") (pintype "passive"))
      (node (ref "R19") (pin "2") (pinfunction "2_2") (pintype "passive"))
    )
    (net (code "47") (name "Net-(R9-Pad2)") (class "Default")
      (node (ref "R9") (pin "2") (pinfunction "2_2") (pintype "passive"))
      (node (ref "V1") (pin "2") (pintype "power_in"))
    )
    (net (code "48") (name "Net-(R10-Pad1)") (class "Default")
      (node (ref "R10") (pin "1") (pinfunction "1_1") (pintype "passive"))
      (node (ref "R15") (pin "2") (pinfunction "2_2") (pintype "passive"))
    )
    (net (code "49") (name "Net-(R10-Pad2)") (class "Default")
      (node (ref "R10") (pin "2") (pinfunction "2_2") (pintype "passive"))
      (node (ref "R11") (pin "2") (pinfunction "2_2") (pintype "passive"))
    )
    (net (code "50") (name "Net-(R14-Pad1)") (class "Default")
      (node (ref "R14") (pin "1") (pinfunction "1_1") (pintype "passive"))
      (node (ref "R15") (pin "1") (pinfunction "1_1") (pintype "passive"))
    )
    (net (code "51") (name "Net-(R14-Pad2)") (class "Default")
      (node (ref "R14") (pin "2") (pinfunction "2_2") (pintype "passive"))
      (node (ref "R9") (pin "1") (pinfunction "1_1") (pintype "passive"))
    )
    (net (code "52") (name "Net-(U2-PROG)") (class "Default")
      (node (ref "R23") (pin "2") (pinfunction "2_2") (pintype "passive"))
      (node (ref "U2") (pin "6") (pinfunction "PROG_6") (pintype "input"))
    )
    (net (code "53") (name "Net-(U2-STAT1)") (class "Default")
      (node (ref "LD3") (pin "K1") (pinfunction "K1_K1") (pintype "passive"))
      (node (ref "U2") (pin "3") (pinfunction "STAT1_3") (pintype "open_collector"))
    )
    (net (code "54") (name "Net-(U2-STAT2)") (class "Default")
      (node (ref "LD3") (pin "K2") (pinfunction "K2_K2") (pintype "passive"))
      (node (ref "U2") (pin "4") (pinfunction "STAT2_4") (pintype "open_collector"))
    )
    (net (code "55") (name "Net-(U2-THERM)") (class "Default")
      (node (ref "R24") (pin "2") (pinfunction "2_2") (pintype "passive"))
      (node (ref "U2") (pin "8") (pinfunction "THERM_8") (pintype "input"))
    )
    (net (code "56") (name "Net-(U2-~{PG})") (class "Default")
      (node (ref "LD3") (pin "K3") (pinfunction "K3_K3") (pintype "passive"))
      (node (ref "U2") (pin "7") (pinfunction "~{PG}_7") (pintype "open_collector"))
    )
    (net (code "57") (name "Net-(VD1-A)") (class "Default")
      (node (ref "C1") (pin "1") (pinfunction "1_1") (pintype "passive"))
      (node (ref "L1") (pin "3") (pinfunction "3_3") (pintype "passive"))
      (node (ref "VD1") (pin "1") (pinfunction "A_1") (pintype "passive"))
    )
    (net (code "58") (name "Net-(VD1-K)") (class "Default")
      (node (ref "C2") (pin "1") (pinfunction "1_1") (pintype "passive"))
      (node (ref "VD1") (pin "2") (pinfunction "K_2") (pintype "passive"))
      (node (ref "VD2") (pin "1") (pinfunction "A_1") (pintype "passive"))
    )
    (net (code "59") (name "Net-(VD2-K)") (class "Default")
      (node (ref "C1") (pin "2") (pinfunction "2_2") (pintype "passive"))
      (node (ref "VD2") (pin "2") (pinfunction "K_2") (pintype "passive"))
      (node (ref "VD3") (pin "1") (pinfunction "A_1") (pintype "passive"))
    )
    (net (code "60") (name "VCC") (class "Default")
      (node (ref "BZ1") (pin "1") (pinfunction "Positive_1") (pintype "passive"))
      (node (ref "C14") (pin "2") (pinfunction "2_2") (pintype "passive"))
      (node (ref "C15") (pin "1") (pinfunction "1_1") (pintype "passive"))
      (node (ref "C16") (pin "2") (pinfunction "2_2") (pintype "passive"))
      (node (ref "C17") (pin "2") (pinfunction "2_2") (pintype "passive"))
      (node (ref "C18") (pin "2") (pinfunction "2_2") (pintype "passive"))
      (node (ref "C19") (pin "2") (pinfunction "2_2") (pintype "passive"))
      (node (ref "C22") (pin "2") (pinfunction "2_2") (pintype "passive"))
      (node (ref "C23") (pin "2") (pinfunction "2_2") (pintype "passive"))
      (node (ref "C24") (pin "2") (pinfunction "2_2") (pintype "passive"))
      (node (ref "DD2") (pin "8") (pinfunction "Vcc_8") (pintype "power_in"))
      (node (ref "DD3") (pin "8") (pinfunction "VCC_8") (pintype "power_in"))
      (node (ref "L1") (pin "2") (pinfunction "2_2") (pintype "passive"))
      (node (ref "P1") (pin "2") (pinfunction "2_2") (pintype "passive"))
      (node (ref "P2") (pin "1") (pinfunction "1_1") (pintype "passive"))
      (node (ref "R25") (pin "2") (pinfunction "2_2") (pintype "passive"))
      (node (ref "R26") (pin "2") (pinfunction "2_2") (pintype "passive"))
      (node (ref "R27") (pin "2") (pinfunction "2_2") (pintype "passive"))
      (node (ref "R28") (pin "2") (pinfunction "2_2") (pintype "passive"))
      (node (ref "R6") (pin "1") (pinfunction "1_1") (pintype "passive"))
      (node (ref "R7") (pin "2") (pinfunction "2_2") (pintype "passive"))
      (node (ref "U1") (pin "17") (pinfunction "VCC_17") (pintype "power_in"))
      (node (ref "U1") (pin "38") (pinfunction "VCC_38") (pintype "power_in"))
      (node (ref "U1") (pin "5") (pinfunction "VCC_5") (pintype "power_in"))
      (node (ref "U2") (pin "10") (pinfunction "VBAT_10") (pintype "power_in"))
      (node (ref "U2") (pin "9") (pinfunction "VBAT_9") (pintype "power_in"))
    )
    (net (code "61") (name "VUSB") (class "Default")
      (node (ref "C13") (pin "1") (pinfunction "1_1") (pintype "passive"))
      (node (ref "C8") (pin "1") (pinfunction "1_1") (pintype "passive"))
      (node (ref "C9") (pin "2") (pinfunction "2_2") (pintype "passive"))
      (node (ref "DD1") (pin "7") (pinfunction "REGIN_7") (pintype "power_in"))
      (node (ref "DD1") (pin "8") (pinfunction "VBUS_8") (pintype "input"))
      (node (ref "J1") (pin "1") (pinfunction "VBUS_1") (pintype "passive"))
      (node (ref "R12") (pin "2") (pinfunction "2_2") (pintype "passive"))
      (node (ref "R20") (pin "1") (pinfunction "1_1") (pintype "passive"))
      (node (ref "R21") (pin "1") (pinfunction "1_1") (pintype "passive"))
      (node (ref "R22") (pin "1") (pinfunction "1_1") (pintype "passive"))
      (node (ref "R8") (pin "2") (pinfunction "2_2") (pintype "passive"))
      (node (ref "U2") (pin "1") (pinfunction "VDD_1") (pintype "power_in"))
      (node (ref "U2") (pin "2") (pinfunction "VDD_2") (pintype "power_in"))
    )
    (net (code "62") (name "unconnected-(DD1-CTS-Pad23)") (class "Default")
      (node (ref "DD1") (pin "23") (pinfunction "CTS_23") (pintype "input"))
    )
    (net (code "63") (name "unconnected-(DD1-DCD-Pad1)") (class "Default")
      (node (ref "DD1") (pin "1") (pinfunction "DCD_1") (pintype "input"))
    )
    (net (code "64") (name "unconnected-(DD1-DSR-Pad27)") (class "Default")
      (node (ref "DD1") (pin "27") (pinfunction "DSR_27") (pintype "input"))
    )
    (net (code "65") (name "unconnected-(DD1-DTR-Pad28)") (class "Default")
      (node (ref "DD1") (pin "28") (pinfunction "DTR_28") (pintype "output"))
    )
    (net (code "66") (name "unconnected-(DD1-RI-Pad2)") (class "Default")
      (node (ref "DD1") (pin "2") (pinfunction "RI_2") (pintype "input"))
    )
    (net (code "67") (name "unconnected-(DD1-RTS-Pad24)") (class "Default")
      (node (ref "DD1") (pin "24") (pinfunction "RTS_24") (pintype "output"))
    )
    (net (code "68") (name "unconnected-(DD1-SUSPEND-Pad12)") (class "Default")
      (node (ref "DD1") (pin "12") (pinfunction "SUSPEND_12") (pintype "output"))
    )
    (net (code "69") (name "unconnected-(DD1-~{SUSPEND}-Pad11)") (class "Default")
      (node (ref "DD1") (pin "11") (pinfunction "~{SUSPEND}_11") (pintype "output"))
    )
    (net (code "70") (name "unconnected-(J1-ID-Pad4)") (class "Default")
      (node (ref "J1") (pin "4") (pinfunction "ID_4") (pintype "passive"))
    )
    (net (code "71") (name "unconnected-(U1-PA5_(ADC5)-Pad32)") (class "Default")
      (node (ref "U1") (pin "32") (pinfunction "PA5_(ADC5)_32") (pintype "bidirectional"))
    )
    (net (code "72") (name "unconnected-(U1-PA6_(ADC6)-Pad31)") (class "Default")
      (node (ref "U1") (pin "31") (pinfunction "PA6_(ADC6)_31") (pintype "bidirectional"))
    )
    (net (code "73") (name "unconnected-(U1-PA7_(ADC7)-Pad30)") (class "Default")
      (node (ref "U1") (pin "30") (pinfunction "PA7_(ADC7)_30") (pintype "bidirectional"))
    )
    (net (code "74") (name "unconnected-(U1-PB0_(XCK{slash}T0)-Pad40)") (class "Default")
      (node (ref "U1") (pin "40") (pinfunction "PB0_(XCK/T0)_40") (pintype "bidirectional"))
    )
    (net (code "75") (name "unconnected-(U1-PB1_(T1)-Pad41)") (class "Default")
      (node (ref "U1") (pin "41") (pinfunction "PB1_(T1)_41") (pintype "bidirectional"))
    )
    (net (code "76") (name "unconnected-(U1-PB3_(OC0{slash}AIN1)-Pad43)") (class "Default")
      (node (ref "U1") (pin "43") (pinfunction "PB3_(OC0/AIN1)_43") (pintype "bidirectional"))
    )
    (net (code "77") (name "unconnected-(U1-PC4_(TDO)-Pad23)") (class "Default")
      (node (ref "U1") (pin "23") (pinfunction "PC4_(TDO)_23") (pintype "bidirectional"))
    )
    (net (code "78") (name "unconnected-(U1-PC5_(TDI)-Pad24)") (class "Default")
      (node (ref "U1") (pin "24") (pinfunction "PC5_(TDI)_24") (pintype "bidirectional"))
    )
    (net (code "79") (name "unconnected-(U1-PC6_(TOSC1)-Pad25)") (class "Default")
      (node (ref "U1") (pin "25") (pinfunction "PC6_(TOSC1)_25") (pintype "bidirectional"))
    )
    (net (code "80") (name "unconnected-(U1-PC7_(TOSC2)-Pad26)") (class "Default")
      (node (ref "U1") (pin "26") (pinfunction "PC7_(TOSC2)_26") (pintype "bidirectional"))
    )
    (net (code "81") (name "unconnected-(U1-PD4_(OC1B)-Pad13)") (class "Default")
      (node (ref "U1") (pin "13") (pinfunction "PD4_(OC1B)_13") (pintype "bidirectional"))
    )
    (net (code "82") (name "unconnected-(U1-PD5_(OC1A)-Pad14)") (class "Default")
      (node (ref "U1") (pin "14") (pinfunction "PD5_(OC1A)_14") (pintype "bidirectional"))
    )
    (net (code "83") (name "unconnected-(U1-PD6_(ICP1)-Pad15)") (class "Default")
      (node (ref "U1") (pin "15") (pinfunction "PD6_(ICP1)_15") (pintype "bidirectional"))
    )
  )
)
